# SCH_OMRA-TI-DRV8874-Module_2025-11-18.net
KiCad netlist of a schematic drawn in EasyEDA
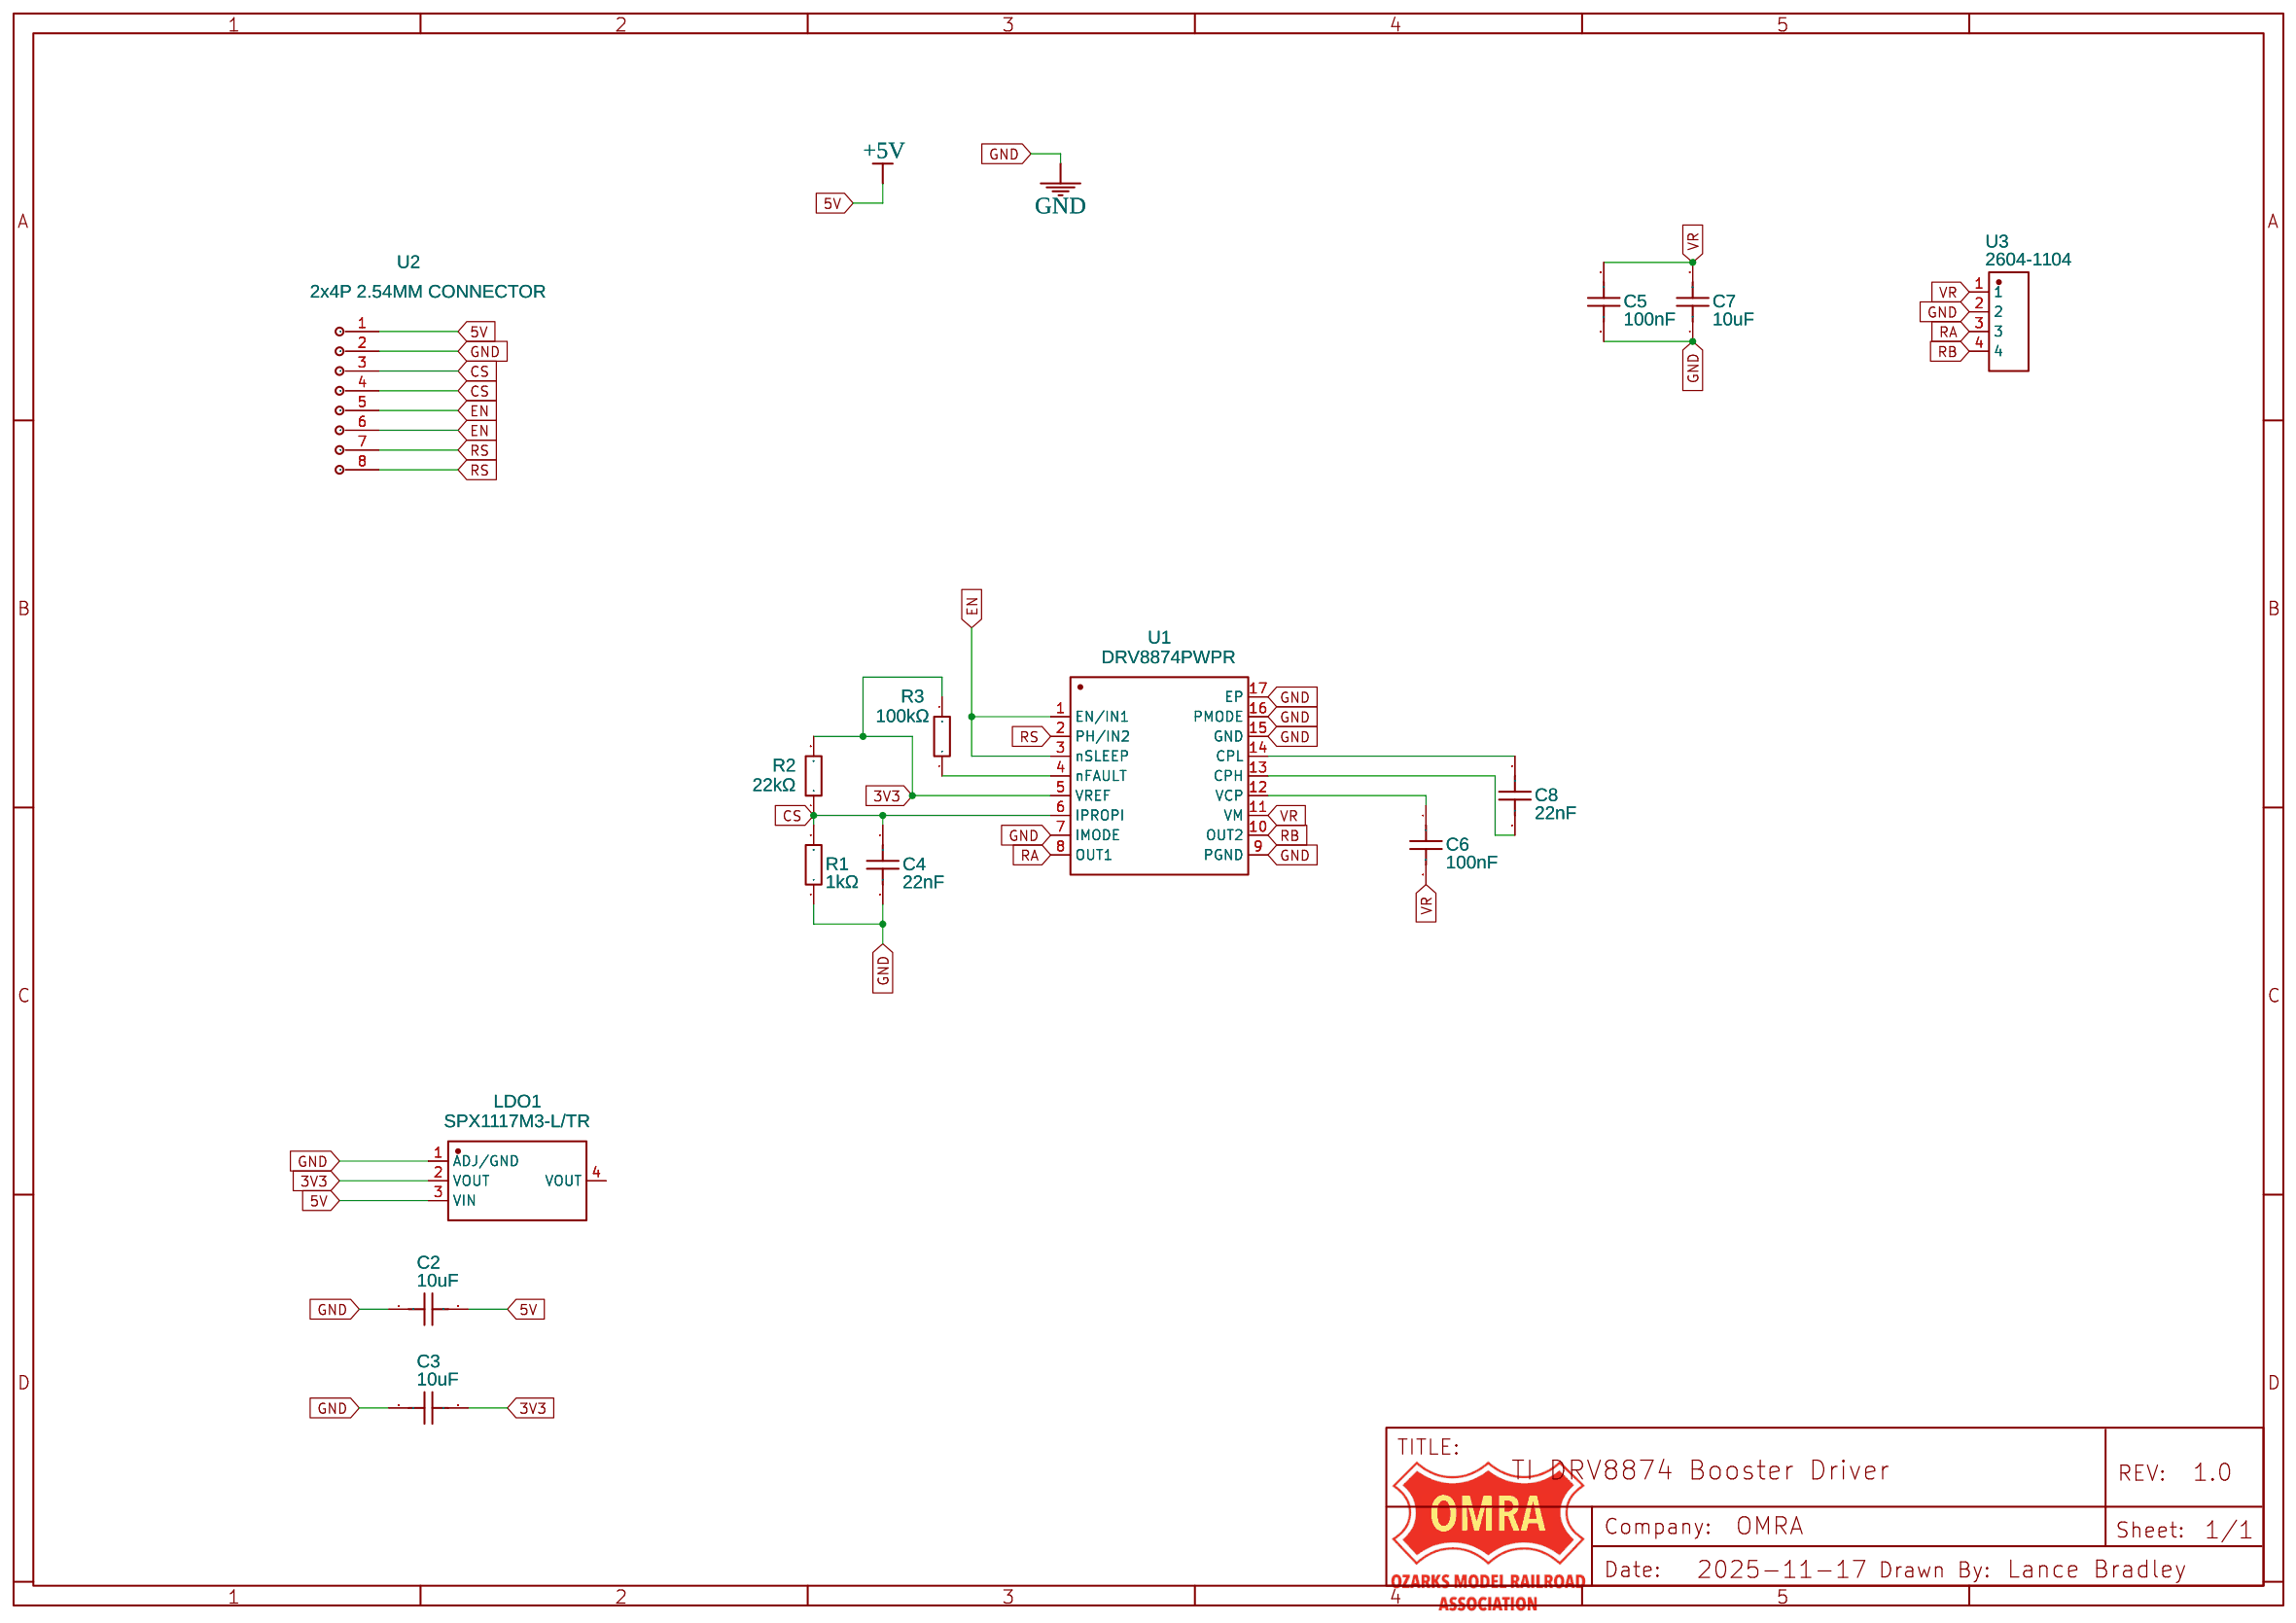
[diagram p0: schematic sheet]

(export (version "E")
  (design (tool "Eeschema 10.0.6"))
  (components
    (comp (ref "C2")
      (value "10uF")
      (fields (field (name "Manufacturer Part") "CGA6P1X8R1E106K250AD") (field (name "Manufacturer") "TDK"))
      (libsource (lib "") (part "CGA6P1X8R1E106K250AD"))
    )
    (comp (ref "C3")
      (value "10uF")
      (fields (field (name "Manufacturer Part") "CGA6P1X8R1E106K250AD") (field (name "Manufacturer") "TDK"))
      (libsource (lib "") (part "CGA6P1X8R1E106K250AD"))
    )
    (comp (ref "C4")
      (value "22nF")
      (fields
        (field (name "Manufacturer Part") "CL05B104KP5VPNC")
        (field (name "Manufacturer") "SAMSUNG(三星)")
      )
      (libsource (lib "") (part "CL05B104KP5VPNC"))
    )
    (comp (ref "C5")
      (value "100nF")
      (fields
        (field (name "Manufacturer Part") "CL05B104KP5VPNC")
        (field (name "Manufacturer") "SAMSUNG(三星)")
      )
      (libsource (lib "") (part "CL05B104KP5VPNC"))
    )
    (comp (ref "C6")
      (value "100nF")
      (fields
        (field (name "Manufacturer Part") "CL05B104KP5VPNC")
        (field (name "Manufacturer") "SAMSUNG(三星)")
      )
      (libsource (lib "") (part "CL05B104KP5VPNC"))
    )
    (comp (ref "C7")
      (value "10uF")
      (fields (field (name "Manufacturer Part") "CGA6P1X8R1E106K250AD") (field (name "Manufacturer") "TDK"))
      (libsource (lib "") (part "CGA6P1X8R1E106K250AD_1"))
    )
    (comp (ref "C8")
      (value "22nF")
      (fields
        (field (name "Manufacturer Part") "CL05B104KP5VPNC")
        (field (name "Manufacturer") "SAMSUNG(三星)")
      )
      (libsource (lib "") (part "CL05B104KP5VPNC"))
    )
    (comp (ref "LDO1")
      (value "SPX1117M3-L/TR")
      (fields (field (name "Manufacturer") "MaxLinear(迈凌)"))
      (libsource (lib "") (part "SPX1117M3-L/TR"))
    )
    (comp (ref "R1")
      (value "1kΩ")
      (fields
        (field (name "Manufacturer Part") "MELF-MFR02041/4WS1KΩFT50")
        (field (name "Manufacturer") "Thunder Component(帝谷)")
      )
      (libsource (lib "") (part "MELF-MFR02041/4WS1KΩFT50"))
    )
    (comp (ref "R2")
      (value "22kΩ")
      (fields
        (field (name "Manufacturer Part") "MELF-MFR02041/4WS1KΩFT50")
        (field (name "Manufacturer") "Thunder Component(帝谷)")
      )
      (libsource (lib "") (part "MELF-MFR02041/4WS1KΩFT50"))
    )
    (comp (ref "R3")
      (value "100kΩ")
      (fields
        (field (name "Manufacturer Part") "MELF-MFR02041/4WS1KΩFT50")
        (field (name "Manufacturer") "Thunder Component(帝谷)")
      )
      (libsource (lib "") (part "MELF-MFR02041/4WS1KΩFT50"))
    )
    (comp (ref "U1")
      (value "DRV8874PWPR")
      (fields (field (name "Manufacturer") "TI(德州仪器)"))
      (libsource (lib "") (part "DRV8874PWPR"))
    )
    (comp (ref "U2") (value "2x4P 2.54MM CONNECTOR") (libsource (lib "") (part "2x4P 2.54MM CONNECTOR")))
    (comp (ref "U3")
      (value "2604-1104")
      (fields (field (name "Manufacturer") "WAGO(万可)"))
      (libsource (lib "") (part "2604-1104"))
    )
  )
  (nets
    (net (code "1") (name "3V3") (class "Default")
      (node (ref "C3") (pin "2") (pinfunction "2_2") (pintype "unspecified"))
      (node (ref "LDO1") (pin "2") (pinfunction "VOUT_2") (pintype "unspecified"))
      (node (ref "R2") (pin "2") (pinfunction "2_2") (pintype "unspecified"))
      (node (ref "R3") (pin "2") (pinfunction "2_2") (pintype "unspecified"))
      (node (ref "U1") (pin "5") (pinfunction "VREF_5") (pintype "unspecified"))
    )
    (net (code "2") (name "5V") (class "Default")
      (node (ref "C2") (pin "2") (pinfunction "2_2") (pintype "unspecified"))
      (node (ref "LDO1") (pin "3") (pinfunction "VIN_3") (pintype "unspecified"))
      (node (ref "U2") (pin "1") (pinfunction "1_1") (pintype "unspecified"))
    )
    (net (code "3") (name "CS") (class "Default")
      (node (ref "C4") (pin "1") (pinfunction "1_1") (pintype "unspecified"))
      (node (ref "R1") (pin "2") (pinfunction "2_2") (pintype "unspecified"))
      (node (ref "R2") (pin "1") (pinfunction "1_1") (pintype "unspecified"))
      (node (ref "U1") (pin "6") (pinfunction "IPROPI_6") (pintype "unspecified"))
      (node (ref "U2") (pin "3") (pinfunction "1_3") (pintype "unspecified"))
      (node (ref "U2") (pin "4") (pinfunction "1_4") (pintype "unspecified"))
    )
    (net (code "4") (name "EN") (class "Default")
      (node (ref "U1") (pin "1") (pinfunction "EN/IN1_1") (pintype "unspecified"))
      (node (ref "U1") (pin "3") (pinfunction "nSLEEP_3") (pintype "unspecified"))
      (node (ref "U2") (pin "5") (pinfunction "1_5") (pintype "unspecified"))
      (node (ref "U2") (pin "6") (pinfunction "1_6") (pintype "unspecified"))
    )
    (net (code "5") (name "GND") (class "Default")
      (node (ref "C2") (pin "1") (pinfunction "1_1") (pintype "unspecified"))
      (node (ref "C3") (pin "1") (pinfunction "1_1") (pintype "unspecified"))
      (node (ref "C4") (pin "2") (pinfunction "2_2") (pintype "unspecified"))
      (node (ref "C5") (pin "2") (pinfunction "2_2") (pintype "unspecified"))
      (node (ref "C7") (pin "1") (pinfunction "1_1") (pintype "unspecified"))
      (node (ref "LDO1") (pin "1") (pinfunction "ADJ/GND_1") (pintype "unspecified"))
      (node (ref "R1") (pin "1") (pinfunction "1_1") (pintype "unspecified"))
      (node (ref "U1") (pin "15") (pinfunction "GND_15") (pintype "unspecified"))
      (node (ref "U1") (pin "16") (pinfunction "PMODE_16") (pintype "unspecified"))
      (node (ref "U1") (pin "17") (pinfunction "EP_17") (pintype "unspecified"))
      (node (ref "U1") (pin "7") (pinfunction "IMODE_7") (pintype "unspecified"))
      (node (ref "U1") (pin "9") (pinfunction "PGND_9") (pintype "unspecified"))
      (node (ref "U2") (pin "2") (pinfunction "1_2") (pintype "unspecified"))
      (node (ref "U3") (pin "2") (pinfunction "2_2") (pintype "unspecified"))
    )
    (net (code "6") (name "Net-(U1-CPH)") (class "Default")
      (node (ref "C8") (pin "2") (pinfunction "2_2") (pintype "unspecified"))
      (node (ref "U1") (pin "13") (pinfunction "CPH_13") (pintype "unspecified"))
    )
    (net (code "7") (name "Net-(U1-CPL)") (class "Default")
      (node (ref "C8") (pin "1") (pinfunction "1_1") (pintype "unspecified"))
      (node (ref "U1") (pin "14") (pinfunction "CPL_14") (pintype "unspecified"))
    )
    (net (code "8") (name "Net-(U1-VCP)") (class "Default")
      (node (ref "C6") (pin "1") (pinfunction "1_1") (pintype "unspecified"))
      (node (ref "U1") (pin "12") (pinfunction "VCP_12") (pintype "unspecified"))
    )
    (net (code "9") (name "Net-(U1-nFAULT)") (class "Default")
      (node (ref "R3") (pin "1") (pinfunction "1_1") (pintype "unspecified"))
      (node (ref "U1") (pin "4") (pinfunction "nFAULT_4") (pintype "unspecified"))
    )
    (net (code "10") (name "RA") (class "Default")
      (node (ref "U1") (pin "8") (pinfunction "OUT1_8") (pintype "unspecified"))
      (node (ref "U3") (pin "3") (pinfunction "3_3") (pintype "unspecified"))
    )
    (net (code "11") (name "RB") (class "Default")
      (node (ref "U1") (pin "10") (pinfunction "OUT2_10") (pintype "unspecified"))
      (node (ref "U3") (pin "4") (pinfunction "4_4") (pintype "unspecified"))
    )
    (net (code "12") (name "RS") (class "Default")
      (node (ref "U1") (pin "2") (pinfunction "PH/IN2_2") (pintype "unspecified"))
      (node (ref "U2") (pin "7") (pinfunction "1_7") (pintype "unspecified"))
      (node (ref "U2") (pin "8") (pinfunction "1_8") (pintype "unspecified"))
    )
    (net (code "13") (name "VR") (class "Default")
      (node (ref "C5") (pin "1") (pinfunction "1_1") (pintype "unspecified"))
      (node (ref "C6") (pin "2") (pinfunction "2_2") (pintype "unspecified"))
      (node (ref "C7") (pin "2") (pinfunction "2_2") (pintype "unspecified"))
      (node (ref "U1") (pin "11") (pinfunction "VM_11") (pintype "unspecified"))
      (node (ref "U3") (pin "1") (pinfunction "1_1") (pintype "unspecified"))
    )
    (net (code "14") (name "unconnected-(LDO1-VOUT-Pad4)") (class "Default")
      (node (ref "LDO1") (pin "4") (pinfunction "VOUT_4") (pintype "unspecified"))
    )
  )
)
